# shield3.net
KiCad netlist of a schematic drawn in EAGLE
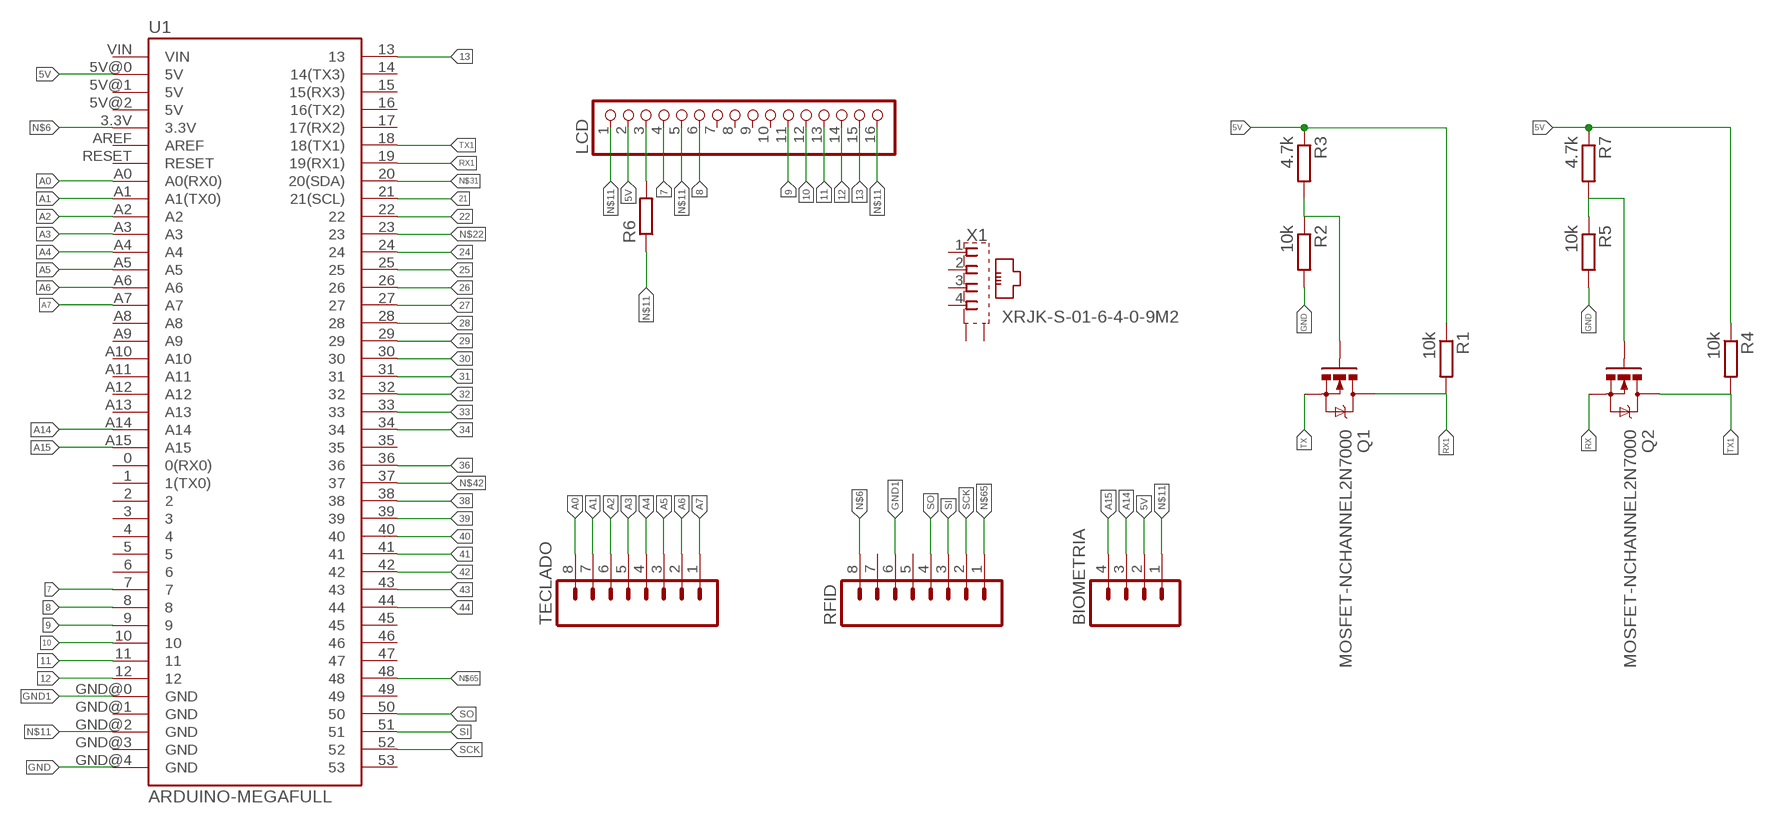
[diagram p0: schematic, sheet 1]

(export (version "E")
  (design (tool "Eeschema 10.0.6"))
  (components
    (comp (ref "BIOMETRIA")
      (value "M04LONGPADS")
      (footprint "eagle-import:1X04_LONGPADS")
      (libsource (lib "eagle-import") (part "M04LONGPADS"))
    )
    (comp (ref "LCD")
      (value "PINHD-1X16")
      (footprint "eagle-import:1X16")
      (libsource (lib "eagle-import") (part "PINHD-1X16"))
    )
    (comp (ref "Q1")
      (value "MOSFET-NCHANNEL2N7000")
      (footprint "eagle-import:TO-92")
      (libsource (lib "eagle-import") (part "MOSFET-NCHANNEL2N7000"))
    )
    (comp (ref "Q2")
      (value "MOSFET-NCHANNEL2N7000")
      (footprint "eagle-import:TO-92")
      (libsource (lib "eagle-import") (part "MOSFET-NCHANNEL2N7000"))
    )
    (comp (ref "R1")
      (value "10k")
      (footprint "eagle-import:0204_7")
      (libsource (lib "eagle-import") (part "R-EU_0204/7"))
    )
    (comp (ref "R2")
      (value "10k")
      (footprint "eagle-import:0204_7")
      (libsource (lib "eagle-import") (part "R-EU_0204/7"))
    )
    (comp (ref "R3")
      (value "4.7k")
      (footprint "eagle-import:0204_7")
      (libsource (lib "eagle-import") (part "R-EU_0204/7"))
    )
    (comp (ref "R4")
      (value "10k")
      (footprint "eagle-import:0204_7")
      (libsource (lib "eagle-import") (part "R-EU_0204/7"))
    )
    (comp (ref "R5")
      (value "10k")
      (footprint "eagle-import:0204_7")
      (libsource (lib "eagle-import") (part "R-EU_0204/7"))
    )
    (comp (ref "R6")
      (value "R-EU_0309/12")
      (footprint "eagle-import:0309_12")
      (libsource (lib "eagle-import") (part "R-EU_0309/12"))
    )
    (comp (ref "R7")
      (value "4.7k")
      (footprint "eagle-import:0204_7")
      (libsource (lib "eagle-import") (part "R-EU_0204/7"))
    )
    (comp (ref "RFID")
      (value "M08LONGPADS")
      (footprint "eagle-import:1X08_LONGPADS")
      (libsource (lib "eagle-import") (part "M08LONGPADS"))
    )
    (comp (ref "TECLADO")
      (value "M08LONGPADS")
      (footprint "eagle-import:1X08_LONGPADS")
      (libsource (lib "eagle-import") (part "M08LONGPADS"))
    )
    (comp (ref "U1")
      (value "ARDUINO-MEGAFULL")
      (footprint "eagle-import:ARDUINO_MEGA")
      (libsource (lib "eagle-import") (part "ARDUINO-MEGAFULL"))
    )
    (comp (ref "X1")
      (value "XRJK-S-01-6-4-0-9M2")
      (footprint "eagle-import:XRJK-S-01-6-4-0-9M2")
      (libsource (lib "eagle-import") (part "XRJK4-0-9M2-S-01-6-"))
    )
  )
  (nets
    (net (code "1") (name "5V") (class "Default")
      (node (ref "BIOMETRIA") (pin "2") (pinfunction "2_2") (pintype "passive"))
      (node (ref "LCD") (pin "2") (pinfunction "2_2") (pintype "passive"))
      (node (ref "R1") (pin "1") (pinfunction "1_1") (pintype "passive"))
      (node (ref "R3") (pin "1") (pinfunction "1_1") (pintype "passive"))
      (node (ref "R4") (pin "1") (pinfunction "1_1") (pintype "passive"))
      (node (ref "R7") (pin "1") (pinfunction "1_1") (pintype "passive"))
      (node (ref "U1") (pin "5V@0") (pinfunction "5V_5V@0") (pintype "bidirectional"))
    )
    (net (code "2") (name "7") (class "Default")
      (node (ref "LCD") (pin "4") (pinfunction "4_4") (pintype "passive"))
      (node (ref "U1") (pin "7") (pinfunction "7_7") (pintype "bidirectional"))
    )
    (net (code "3") (name "8") (class "Default")
      (node (ref "LCD") (pin "6") (pinfunction "6_6") (pintype "passive"))
      (node (ref "U1") (pin "8") (pinfunction "8_8") (pintype "bidirectional"))
    )
    (net (code "4") (name "9") (class "Default")
      (node (ref "LCD") (pin "11") (pinfunction "11_11") (pintype "passive"))
      (node (ref "U1") (pin "9") (pinfunction "9_9") (pintype "bidirectional"))
    )
    (net (code "5") (name "10") (class "Default")
      (node (ref "LCD") (pin "12") (pinfunction "12_12") (pintype "passive"))
      (node (ref "U1") (pin "10") (pinfunction "10_10") (pintype "bidirectional"))
    )
    (net (code "6") (name "11") (class "Default")
      (node (ref "LCD") (pin "13") (pinfunction "13_13") (pintype "passive"))
      (node (ref "U1") (pin "11") (pinfunction "11_11") (pintype "bidirectional"))
    )
    (net (code "7") (name "12") (class "Default")
      (node (ref "LCD") (pin "14") (pinfunction "14_14") (pintype "passive"))
      (node (ref "U1") (pin "12") (pinfunction "12_12") (pintype "bidirectional"))
    )
    (net (code "8") (name "13") (class "Default")
      (node (ref "LCD") (pin "15") (pinfunction "15_15") (pintype "passive"))
      (node (ref "U1") (pin "13") (pinfunction "13_13") (pintype "bidirectional"))
    )
    (net (code "9") (name "21") (class "Default")
      (node (ref "U1") (pin "21") (pinfunction "21(SCL)_21") (pintype "bidirectional"))
    )
    (net (code "10") (name "22") (class "Default")
      (node (ref "U1") (pin "22") (pinfunction "22_22") (pintype "bidirectional"))
    )
    (net (code "11") (name "24") (class "Default")
      (node (ref "U1") (pin "24") (pinfunction "24_24") (pintype "bidirectional"))
    )
    (net (code "12") (name "25") (class "Default")
      (node (ref "U1") (pin "25") (pinfunction "25_25") (pintype "bidirectional"))
    )
    (net (code "13") (name "26") (class "Default")
      (node (ref "U1") (pin "26") (pinfunction "26_26") (pintype "bidirectional"))
    )
    (net (code "14") (name "27") (class "Default")
      (node (ref "U1") (pin "27") (pinfunction "27_27") (pintype "bidirectional"))
    )
    (net (code "15") (name "28") (class "Default")
      (node (ref "U1") (pin "28") (pinfunction "28_28") (pintype "bidirectional"))
    )
    (net (code "16") (name "29") (class "Default")
      (node (ref "U1") (pin "29") (pinfunction "29_29") (pintype "bidirectional"))
    )
    (net (code "17") (name "30") (class "Default")
      (node (ref "U1") (pin "30") (pinfunction "30_30") (pintype "bidirectional"))
    )
    (net (code "18") (name "31") (class "Default")
      (node (ref "U1") (pin "31") (pinfunction "31_31") (pintype "bidirectional"))
    )
    (net (code "19") (name "32") (class "Default")
      (node (ref "U1") (pin "32") (pinfunction "32_32") (pintype "bidirectional"))
    )
    (net (code "20") (name "33") (class "Default")
      (node (ref "U1") (pin "33") (pinfunction "33_33") (pintype "bidirectional"))
    )
    (net (code "21") (name "34") (class "Default")
      (node (ref "U1") (pin "34") (pinfunction "34_34") (pintype "bidirectional"))
    )
    (net (code "22") (name "36") (class "Default")
      (node (ref "U1") (pin "36") (pinfunction "36_36") (pintype "bidirectional"))
    )
    (net (code "23") (name "38") (class "Default")
      (node (ref "U1") (pin "38") (pinfunction "38_38") (pintype "bidirectional"))
    )
    (net (code "24") (name "39") (class "Default")
      (node (ref "U1") (pin "39") (pinfunction "39_39") (pintype "bidirectional"))
    )
    (net (code "25") (name "40") (class "Default")
      (node (ref "U1") (pin "40") (pinfunction "40_40") (pintype "bidirectional"))
    )
    (net (code "26") (name "41") (class "Default")
      (node (ref "U1") (pin "41") (pinfunction "41_41") (pintype "bidirectional"))
    )
    (net (code "27") (name "42") (class "Default")
      (node (ref "U1") (pin "42") (pinfunction "42_42") (pintype "bidirectional"))
    )
    (net (code "28") (name "43") (class "Default")
      (node (ref "U1") (pin "43") (pinfunction "43_43") (pintype "bidirectional"))
    )
    (net (code "29") (name "44") (class "Default")
      (node (ref "U1") (pin "44") (pinfunction "44_44") (pintype "bidirectional"))
    )
    (net (code "30") (name "A0") (class "Default")
      (node (ref "TECLADO") (pin "8") (pinfunction "8_8") (pintype "passive"))
      (node (ref "U1") (pin "A0") (pinfunction "A0(RX0)_A0") (pintype "bidirectional"))
    )
    (net (code "31") (name "A1") (class "Default")
      (node (ref "TECLADO") (pin "7") (pinfunction "7_7") (pintype "passive"))
      (node (ref "U1") (pin "A1") (pinfunction "A1(TX0)_A1") (pintype "bidirectional"))
    )
    (net (code "32") (name "A2") (class "Default")
      (node (ref "TECLADO") (pin "6") (pinfunction "6_6") (pintype "passive"))
      (node (ref "U1") (pin "A2") (pinfunction "A2_A2") (pintype "bidirectional"))
    )
    (net (code "33") (name "A3") (class "Default")
      (node (ref "TECLADO") (pin "5") (pinfunction "5_5") (pintype "passive"))
      (node (ref "U1") (pin "A3") (pinfunction "A3_A3") (pintype "bidirectional"))
    )
    (net (code "34") (name "A4") (class "Default")
      (node (ref "TECLADO") (pin "4") (pinfunction "4_4") (pintype "passive"))
      (node (ref "U1") (pin "A4") (pinfunction "A4_A4") (pintype "bidirectional"))
    )
    (net (code "35") (name "A5") (class "Default")
      (node (ref "TECLADO") (pin "3") (pinfunction "3_3") (pintype "passive"))
      (node (ref "U1") (pin "A5") (pinfunction "A5_A5") (pintype "bidirectional"))
    )
    (net (code "36") (name "A6") (class "Default")
      (node (ref "TECLADO") (pin "2") (pinfunction "2_2") (pintype "passive"))
      (node (ref "U1") (pin "A6") (pinfunction "A6_A6") (pintype "bidirectional"))
    )
    (net (code "37") (name "A7") (class "Default")
      (node (ref "TECLADO") (pin "1") (pinfunction "1_1") (pintype "passive"))
      (node (ref "U1") (pin "A7") (pinfunction "A7_A7") (pintype "bidirectional"))
    )
    (net (code "38") (name "A14") (class "Default")
      (node (ref "BIOMETRIA") (pin "3") (pinfunction "3_3") (pintype "passive"))
      (node (ref "U1") (pin "A14") (pinfunction "A14_A14") (pintype "bidirectional"))
    )
    (net (code "39") (name "A15") (class "Default")
      (node (ref "BIOMETRIA") (pin "4") (pinfunction "4_4") (pintype "passive"))
      (node (ref "U1") (pin "A15") (pinfunction "A15_A15") (pintype "bidirectional"))
    )
    (net (code "40") (name "GND") (class "Default")
      (node (ref "R2") (pin "2") (pinfunction "2_2") (pintype "passive"))
      (node (ref "R5") (pin "2") (pinfunction "2_2") (pintype "passive"))
      (node (ref "U1") (pin "GND@4") (pinfunction "GND_GND@4") (pintype "bidirectional"))
    )
    (net (code "41") (name "GND1") (class "Default")
      (node (ref "RFID") (pin "6") (pinfunction "6_6") (pintype "passive"))
      (node (ref "U1") (pin "GND@0") (pinfunction "GND_GND@0") (pintype "bidirectional"))
    )
    (net (code "42") (name "N$6") (class "Default")
      (node (ref "RFID") (pin "8") (pinfunction "8_8") (pintype "passive"))
      (node (ref "U1") (pin "3.3V") (pinfunction "3.3V_3.3V") (pintype "bidirectional"))
    )
    (net (code "43") (name "N$11") (class "Default")
      (node (ref "BIOMETRIA") (pin "1") (pinfunction "1_1") (pintype "passive"))
      (node (ref "LCD") (pin "1") (pinfunction "1_1") (pintype "passive"))
      (node (ref "LCD") (pin "16") (pinfunction "16_16") (pintype "passive"))
      (node (ref "LCD") (pin "5") (pinfunction "5_5") (pintype "passive"))
      (node (ref "R6") (pin "1") (pinfunction "1_1") (pintype "passive"))
      (node (ref "U1") (pin "GND@2") (pinfunction "GND_GND@2") (pintype "bidirectional"))
    )
    (net (code "44") (name "N$22") (class "Default")
      (node (ref "U1") (pin "23") (pinfunction "23_23") (pintype "bidirectional"))
    )
    (net (code "45") (name "N$31") (class "Default")
      (node (ref "U1") (pin "20") (pinfunction "20(SDA)_20") (pintype "bidirectional"))
    )
    (net (code "46") (name "N$42") (class "Default")
      (node (ref "U1") (pin "37") (pinfunction "37_37") (pintype "bidirectional"))
    )
    (net (code "47") (name "N$65") (class "Default")
      (node (ref "RFID") (pin "1") (pinfunction "1_1") (pintype "passive"))
      (node (ref "U1") (pin "48") (pinfunction "48_48") (pintype "bidirectional"))
    )
    (net (code "48") (name "Net-(LCD-Pad3)") (class "Default")
      (node (ref "LCD") (pin "3") (pinfunction "3_3") (pintype "passive"))
      (node (ref "R6") (pin "2") (pinfunction "2_2") (pintype "passive"))
    )
    (net (code "49") (name "Net-(Q1-G)") (class "Default")
      (node (ref "Q1") (pin "2") (pinfunction "G_2") (pintype "passive"))
      (node (ref "R2") (pin "1") (pinfunction "1_1") (pintype "passive"))
      (node (ref "R3") (pin "2") (pinfunction "2_2") (pintype "passive"))
    )
    (net (code "50") (name "Net-(Q2-G)") (class "Default")
      (node (ref "Q2") (pin "2") (pinfunction "G_2") (pintype "passive"))
      (node (ref "R5") (pin "1") (pinfunction "1_1") (pintype "passive"))
      (node (ref "R7") (pin "2") (pinfunction "2_2") (pintype "passive"))
    )
    (net (code "51") (name "RX") (class "Default")
      (node (ref "Q2") (pin "1") (pinfunction "S_1") (pintype "passive"))
    )
    (net (code "52") (name "RX1") (class "Default")
      (node (ref "Q1") (pin "3") (pinfunction "D_3") (pintype "passive"))
      (node (ref "R1") (pin "2") (pinfunction "2_2") (pintype "passive"))
      (node (ref "U1") (pin "19") (pinfunction "19(RX1)_19") (pintype "bidirectional"))
    )
    (net (code "53") (name "SCK") (class "Default")
      (node (ref "RFID") (pin "2") (pinfunction "2_2") (pintype "passive"))
      (node (ref "U1") (pin "52") (pinfunction "52_52") (pintype "bidirectional"))
    )
    (net (code "54") (name "SI") (class "Default")
      (node (ref "RFID") (pin "3") (pinfunction "3_3") (pintype "passive"))
      (node (ref "U1") (pin "51") (pinfunction "51_51") (pintype "bidirectional"))
    )
    (net (code "55") (name "SO") (class "Default")
      (node (ref "RFID") (pin "4") (pinfunction "4_4") (pintype "passive"))
      (node (ref "U1") (pin "50") (pinfunction "50_50") (pintype "bidirectional"))
    )
    (net (code "56") (name "TX") (class "Default")
      (node (ref "Q1") (pin "1") (pinfunction "S_1") (pintype "passive"))
    )
    (net (code "57") (name "TX1") (class "Default")
      (node (ref "Q2") (pin "3") (pinfunction "D_3") (pintype "passive"))
      (node (ref "R4") (pin "2") (pinfunction "2_2") (pintype "passive"))
      (node (ref "U1") (pin "18") (pinfunction "18(TX1)_18") (pintype "bidirectional"))
    )
    (net (code "58") (name "unconnected-(LCD-Pad7)") (class "Default")
      (node (ref "LCD") (pin "7") (pinfunction "7_7") (pintype "passive"))
    )
    (net (code "59") (name "unconnected-(LCD-Pad8)") (class "Default")
      (node (ref "LCD") (pin "8") (pinfunction "8_8") (pintype "passive"))
    )
    (net (code "60") (name "unconnected-(LCD-Pad9)") (class "Default")
      (node (ref "LCD") (pin "9") (pinfunction "9_9") (pintype "passive"))
    )
    (net (code "61") (name "unconnected-(LCD-Pad10)") (class "Default")
      (node (ref "LCD") (pin "10") (pinfunction "10_10") (pintype "passive"))
    )
    (net (code "62") (name "unconnected-(RFID-Pad5)") (class "Default")
      (node (ref "RFID") (pin "5") (pinfunction "5_5") (pintype "passive"))
    )
    (net (code "63") (name "unconnected-(RFID-Pad7)") (class "Default")
      (node (ref "RFID") (pin "7") (pinfunction "7_7") (pintype "passive"))
    )
    (net (code "64") (name "unconnected-(U1-0(RX0)-Pad0)") (class "Default")
      (node (ref "U1") (pin "0") (pinfunction "0(RX0)_0") (pintype "bidirectional"))
    )
    (net (code "65") (name "unconnected-(U1-1(TX0)-Pad1)") (class "Default")
      (node (ref "U1") (pin "1") (pinfunction "1(TX0)_1") (pintype "bidirectional"))
    )
    (net (code "66") (name "unconnected-(U1-5V-Pad5V@1)") (class "Default")
      (node (ref "U1") (pin "5V@1") (pinfunction "5V_5V@1") (pintype "bidirectional"))
    )
    (net (code "67") (name "unconnected-(U1-5V-Pad5V@2)") (class "Default")
      (node (ref "U1") (pin "5V@2") (pinfunction "5V_5V@2") (pintype "bidirectional"))
    )
    (net (code "68") (name "unconnected-(U1-14(TX3)-Pad14)") (class "Default")
      (node (ref "U1") (pin "14") (pinfunction "14(TX3)_14") (pintype "bidirectional"))
    )
    (net (code "69") (name "unconnected-(U1-15(RX3)-Pad15)") (class "Default")
      (node (ref "U1") (pin "15") (pinfunction "15(RX3)_15") (pintype "bidirectional"))
    )
    (net (code "70") (name "unconnected-(U1-16(TX2)-Pad16)") (class "Default")
      (node (ref "U1") (pin "16") (pinfunction "16(TX2)_16") (pintype "bidirectional"))
    )
    (net (code "71") (name "unconnected-(U1-17(RX2)-Pad17)") (class "Default")
      (node (ref "U1") (pin "17") (pinfunction "17(RX2)_17") (pintype "bidirectional"))
    )
    (net (code "72") (name "unconnected-(U1-GND-PadGND@1)") (class "Default")
      (node (ref "U1") (pin "GND@1") (pinfunction "GND_GND@1") (pintype "bidirectional"))
    )
    (net (code "73") (name "unconnected-(U1-GND-PadGND@3)") (class "Default")
      (node (ref "U1") (pin "GND@3") (pinfunction "GND_GND@3") (pintype "bidirectional"))
    )
    (net (code "74") (name "unconnected-(U1-Pad2)") (class "Default")
      (node (ref "U1") (pin "2") (pinfunction "2_2") (pintype "bidirectional"))
    )
    (net (code "75") (name "unconnected-(U1-Pad3)") (class "Default")
      (node (ref "U1") (pin "3") (pinfunction "3_3") (pintype "bidirectional"))
    )
    (net (code "76") (name "unconnected-(U1-Pad4)") (class "Default")
      (node (ref "U1") (pin "4") (pinfunction "4_4") (pintype "bidirectional"))
    )
    (net (code "77") (name "unconnected-(U1-Pad5)") (class "Default")
      (node (ref "U1") (pin "5") (pinfunction "5_5") (pintype "bidirectional"))
    )
    (net (code "78") (name "unconnected-(U1-Pad6)") (class "Default")
      (node (ref "U1") (pin "6") (pinfunction "6_6") (pintype "bidirectional"))
    )
    (net (code "79") (name "unconnected-(U1-Pad35)") (class "Default")
      (node (ref "U1") (pin "35") (pinfunction "35_35") (pintype "bidirectional"))
    )
    (net (code "80") (name "unconnected-(U1-Pad45)") (class "Default")
      (node (ref "U1") (pin "45") (pinfunction "45_45") (pintype "bidirectional"))
    )
    (net (code "81") (name "unconnected-(U1-Pad46)") (class "Default")
      (node (ref "U1") (pin "46") (pinfunction "46_46") (pintype "bidirectional"))
    )
    (net (code "82") (name "unconnected-(U1-Pad47)") (class "Default")
      (node (ref "U1") (pin "47") (pinfunction "47_47") (pintype "bidirectional"))
    )
    (net (code "83") (name "unconnected-(U1-Pad49)") (class "Default")
      (node (ref "U1") (pin "49") (pinfunction "49_49") (pintype "bidirectional"))
    )
    (net (code "84") (name "unconnected-(U1-Pad53)") (class "Default")
      (node (ref "U1") (pin "53") (pinfunction "53_53") (pintype "bidirectional"))
    )
    (net (code "85") (name "unconnected-(U1-PadA8)") (class "Default")
      (node (ref "U1") (pin "A8") (pinfunction "A8_A8") (pintype "bidirectional"))
    )
    (net (code "86") (name "unconnected-(U1-PadA9)") (class "Default")
      (node (ref "U1") (pin "A9") (pinfunction "A9_A9") (pintype "bidirectional"))
    )
    (net (code "87") (name "unconnected-(U1-PadA10)") (class "Default")
      (node (ref "U1") (pin "A10") (pinfunction "A10_A10") (pintype "bidirectional"))
    )
    (net (code "88") (name "unconnected-(U1-PadA11)") (class "Default")
      (node (ref "U1") (pin "A11") (pinfunction "A11_A11") (pintype "bidirectional"))
    )
    (net (code "89") (name "unconnected-(U1-PadA12)") (class "Default")
      (node (ref "U1") (pin "A12") (pinfunction "A12_A12") (pintype "bidirectional"))
    )
    (net (code "90") (name "unconnected-(U1-PadA13)") (class "Default")
      (node (ref "U1") (pin "A13") (pinfunction "A13_A13") (pintype "bidirectional"))
    )
    (net (code "91") (name "unconnected-(U1-PadAREF)") (class "Default")
      (node (ref "U1") (pin "AREF") (pinfunction "AREF_AREF") (pintype "bidirectional"))
    )
    (net (code "92") (name "unconnected-(U1-PadRESET)") (class "Default")
      (node (ref "U1") (pin "RESET") (pinfunction "RESET_RESET") (pintype "bidirectional"))
    )
    (net (code "93") (name "unconnected-(U1-PadVIN)") (class "Default")
      (node (ref "U1") (pin "VIN") (pinfunction "VIN_VIN") (pintype "bidirectional"))
    )
    (net (code "94") (name "unconnected-(X1-Pad1)") (class "Default")
      (node (ref "X1") (pin "1") (pinfunction "1_1") (pintype "passive"))
    )
    (net (code "95") (name "unconnected-(X1-Pad2)") (class "Default")
      (node (ref "X1") (pin "2") (pinfunction "2_2") (pintype "passive"))
    )
    (net (code "96") (name "unconnected-(X1-Pad3)") (class "Default")
      (node (ref "X1") (pin "3") (pinfunction "3_3") (pintype "passive"))
    )
    (net (code "97") (name "unconnected-(X1-Pad4)") (class "Default")
      (node (ref "X1") (pin "4") (pinfunction "4_4") (pintype "passive"))
    )
    (net (code "98") (name "unconnected-(X1-S-PadS1)") (class "Default")
      (node (ref "X1") (pin "S1") (pinfunction "S_S1") (pintype "passive"))
    )
    (net (code "99") (name "unconnected-(X1-S-PadS2)") (class "Default")
      (node (ref "X1") (pin "S2") (pinfunction "S_S2") (pintype "passive"))
    )
  )
)
